# MCU_Module_V1.net
KiCad netlist of a schematic drawn in EAGLE
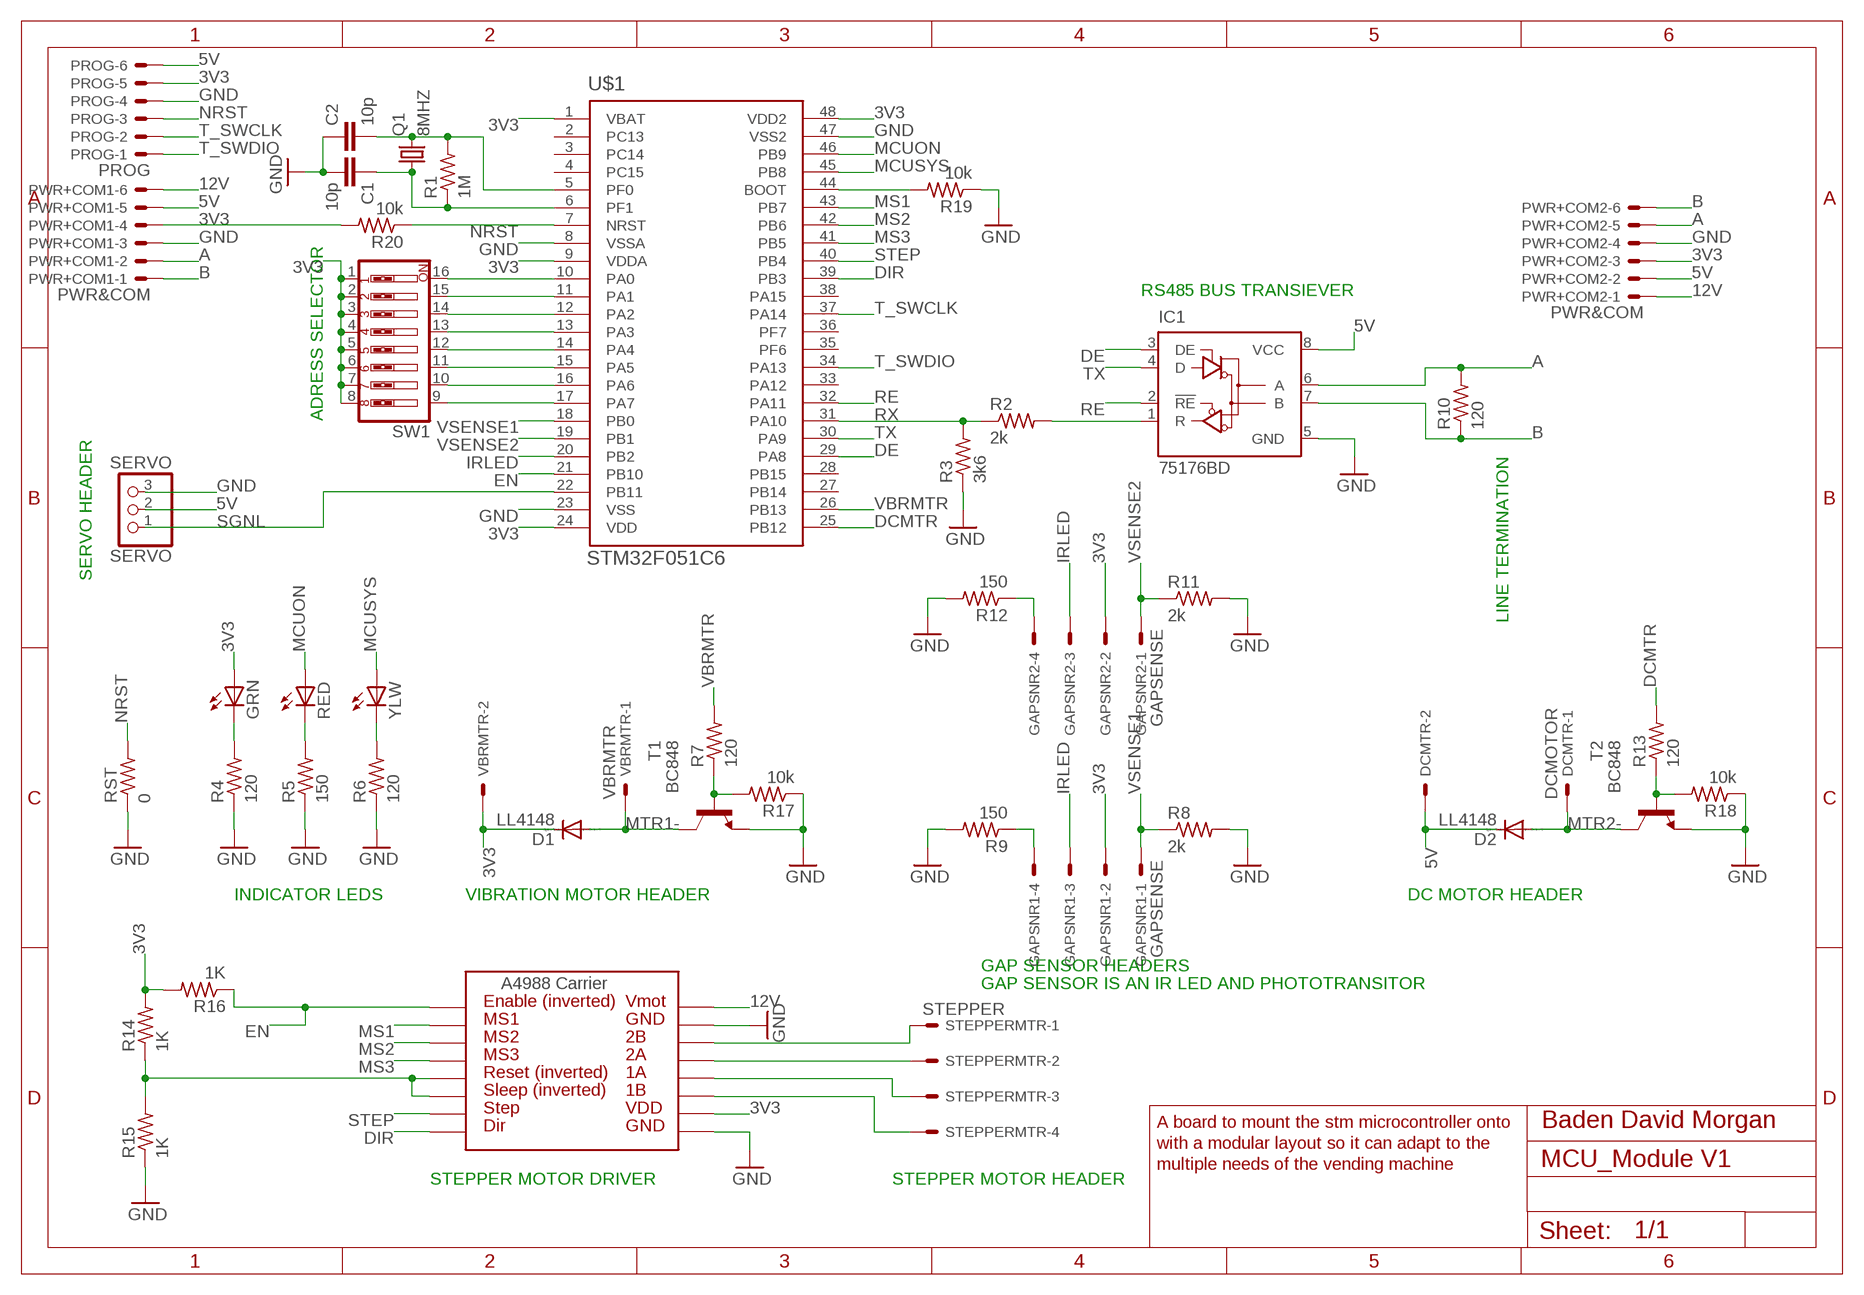
[diagram p0: schematic, sheet 1]

(export (version "E")
  (design (tool "Eeschema 10.0.6"))
  (components
    (comp (ref "C1")
      (value "10p")
      (footprint "eagle-import:C0805")
      (libsource (lib "eagle-import") (part "C-EUC0805"))
    )
    (comp (ref "C2")
      (value "10p")
      (footprint "eagle-import:C0805")
      (libsource (lib "eagle-import") (part "C-EUC0805"))
    )
    (comp (ref "D1")
      (value "LL4148")
      (footprint "eagle-import:SOD80C")
      (libsource (lib "eagle-import") (part "PMLL4150"))
    )
    (comp (ref "D2")
      (value "LL4148")
      (footprint "eagle-import:SOD80C")
      (libsource (lib "eagle-import") (part "PMLL4150"))
    )
    (comp (ref "DCMTR")
      (value "DCMOTOR")
      (footprint "eagle-import:6410-02")
      (libsource (lib "eagle-import") (part "22-?-0227-2021"))
    )
    (comp (ref "GAPSNR1")
      (value "GAPSENSE")
      (footprint "eagle-import:6410-04")
      (libsource (lib "eagle-import") (part "22-?-0427-2041"))
    )
    (comp (ref "GAPSNR2")
      (value "GAPSENSE")
      (footprint "eagle-import:6410-04")
      (libsource (lib "eagle-import") (part "22-?-0427-2041"))
    )
    (comp (ref "GRN")
      (value "LEDSML1206")
      (footprint "eagle-import:SML1206")
      (libsource (lib "eagle-import") (part "LEDSML1206"))
    )
    (comp (ref "IC1")
      (value "75176BD")
      (footprint "eagle-import:D_R-PDSO-G8")
      (libsource (lib "eagle-import") (part "75176AD"))
    )
    (comp (ref "PROG")
      (value "PROG")
      (footprint "eagle-import:6410-06")
      (libsource (lib "eagle-import") (part "22-?-0627-2061"))
    )
    (comp (ref "PWR+COM1")
      (value "PWR&COM")
      (footprint "eagle-import:7395-06")
      (libsource (lib "eagle-import") (part "22-?-0605-7068"))
    )
    (comp (ref "PWR+COM2")
      (value "PWR&COM")
      (footprint "eagle-import:7395-06")
      (libsource (lib "eagle-import") (part "22-?-0605-7068"))
    )
    (comp (ref "Q1")
      (value "8MHZ")
      (footprint "eagle-import:SM49")
      (libsource (lib "eagle-import") (part "CRYSTALSM49"))
    )
    (comp (ref "R1")
      (value "1M")
      (footprint "eagle-import:R0805")
      (libsource (lib "eagle-import") (part "R-US_R0805"))
    )
    (comp (ref "R2")
      (value "2k")
      (footprint "eagle-import:R0805")
      (libsource (lib "eagle-import") (part "resistor_R-US_R0805"))
    )
    (comp (ref "R3")
      (value "3k6")
      (footprint "eagle-import:R0805")
      (libsource (lib "eagle-import") (part "resistor_R-US_R0805"))
    )
    (comp (ref "R4")
      (value "120")
      (footprint "eagle-import:R0805")
      (libsource (lib "eagle-import") (part "R-US_R0805"))
    )
    (comp (ref "R5")
      (value "150")
      (footprint "eagle-import:R0805")
      (libsource (lib "eagle-import") (part "R-US_R0805"))
    )
    (comp (ref "R6")
      (value "120")
      (footprint "eagle-import:R0805")
      (libsource (lib "eagle-import") (part "R-US_R0805"))
    )
    (comp (ref "R7")
      (value "120")
      (footprint "eagle-import:R0805")
      (libsource (lib "eagle-import") (part "R-US_R0805"))
    )
    (comp (ref "R8")
      (value "2k")
      (footprint "eagle-import:R0805")
      (libsource (lib "eagle-import") (part "resistor_R-US_R0805"))
    )
    (comp (ref "R9")
      (value "150")
      (footprint "eagle-import:R0805")
      (libsource (lib "eagle-import") (part "R-US_R0805"))
    )
    (comp (ref "R10")
      (value "120")
      (footprint "eagle-import:R0805")
      (libsource (lib "eagle-import") (part "resistor_R-US_R0805"))
    )
    (comp (ref "R11")
      (value "2k")
      (footprint "eagle-import:R0805")
      (libsource (lib "eagle-import") (part "resistor_R-US_R0805"))
    )
    (comp (ref "R12")
      (value "150")
      (footprint "eagle-import:R0805")
      (libsource (lib "eagle-import") (part "R-US_R0805"))
    )
    (comp (ref "R13")
      (value "120")
      (footprint "eagle-import:R0805")
      (libsource (lib "eagle-import") (part "R-US_R0805"))
    )
    (comp (ref "R14")
      (value "1K")
      (footprint "eagle-import:R0805")
      (libsource (lib "eagle-import") (part "R-US_R0805"))
    )
    (comp (ref "R15")
      (value "1K")
      (footprint "eagle-import:R0805")
      (libsource (lib "eagle-import") (part "R-US_R0805"))
    )
    (comp (ref "R16")
      (value "1K")
      (footprint "eagle-import:R0805")
      (libsource (lib "eagle-import") (part "R-US_R0805"))
    )
    (comp (ref "R17")
      (value "10k")
      (footprint "eagle-import:R0805")
      (libsource (lib "eagle-import") (part "R-US_R0805"))
    )
    (comp (ref "R18")
      (value "10k")
      (footprint "eagle-import:R0805")
      (libsource (lib "eagle-import") (part "R-US_R0805"))
    )
    (comp (ref "R19")
      (value "10k")
      (footprint "eagle-import:R0805")
      (libsource (lib "eagle-import") (part "R-US_R0805"))
    )
    (comp (ref "R20")
      (value "10k")
      (footprint "eagle-import:R0805")
      (libsource (lib "eagle-import") (part "R-US_R0805"))
    )
    (comp (ref "RED")
      (value "LEDSML1206")
      (footprint "eagle-import:SML1206")
      (libsource (lib "eagle-import") (part "LEDSML1206"))
    )
    (comp (ref "RST")
      (value "0")
      (footprint "eagle-import:R0805")
      (libsource (lib "eagle-import") (part "R-US_R0805"))
    )
    (comp (ref "SERVO")
      (value "SERVO")
      (footprint "eagle-import:1X03")
      (libsource (lib "eagle-import") (part "PINHD-1X3"))
    )
    (comp (ref "STEPPERMTR")
      (value "STEPPER")
      (footprint "eagle-import:6410-04")
      (libsource (lib "eagle-import") (part "22-?-0427-2041"))
    )
    (comp (ref "SW1")
      (value "SW_DIP-8")
      (footprint "eagle-import:EDG-08")
      (libsource (lib "eagle-import") (part "SW_DIP-8"))
    )
    (comp (ref "T1")
      (value "BC848")
      (footprint "eagle-import:SOT23")
      (libsource (lib "eagle-import") (part "BC848"))
    )
    (comp (ref "T2")
      (value "BC848")
      (footprint "eagle-import:SOT23")
      (libsource (lib "eagle-import") (part "BC848"))
    )
    (comp (ref "U$1")
      (value "STM32F051C6")
      (footprint "eagle-import:QFP50P900X900X160-48N")
      (libsource (lib "eagle-import") (part "STM32F051C6"))
    )
    (comp (ref "U$2")
      (value "A4983CARRIER")
      (footprint "eagle-import:A4988BREAKOUT")
      (libsource (lib "eagle-import") (part "A4983CARRIER"))
    )
    (comp (ref "VBRMTR")
      (value "VBRMTR")
      (footprint "eagle-import:6410-02")
      (libsource (lib "eagle-import") (part "22-?-0227-2021"))
    )
    (comp (ref "YLW")
      (value "LEDSML1206")
      (footprint "eagle-import:SML1206")
      (libsource (lib "eagle-import") (part "LEDSML1206"))
    )
  )
  (nets
    (net (code "1") (name "/3V3") (class "Default")
      (node (ref "D1") (pin "C") (pinfunction "C_C") (pintype "passive"))
      (node (ref "GAPSNR1") (pin "2") (pinfunction "S_2") (pintype "passive"))
      (node (ref "GAPSNR2") (pin "2") (pinfunction "S_2") (pintype "passive"))
      (node (ref "GRN") (pin "A") (pinfunction "A_A") (pintype "passive"))
      (node (ref "PROG") (pin "5") (pinfunction "S_5") (pintype "passive"))
      (node (ref "PWR+COM1") (pin "4") (pinfunction "S_4") (pintype "passive"))
      (node (ref "PWR+COM2") (pin "3") (pinfunction "S_3") (pintype "passive"))
      (node (ref "R14") (pin "2") (pinfunction "2_2") (pintype "passive"))
      (node (ref "R16") (pin "2") (pinfunction "2_2") (pintype "passive"))
      (node (ref "R20") (pin "2") (pinfunction "2_2") (pintype "passive"))
      (node (ref "SW1") (pin "1") (pinfunction "1_1") (pintype "passive"))
      (node (ref "SW1") (pin "2") (pinfunction "2_2") (pintype "passive"))
      (node (ref "SW1") (pin "3") (pinfunction "3_3") (pintype "passive"))
      (node (ref "SW1") (pin "4") (pinfunction "4_4") (pintype "passive"))
      (node (ref "SW1") (pin "5") (pinfunction "5_5") (pintype "passive"))
      (node (ref "SW1") (pin "6") (pinfunction "6_6") (pintype "passive"))
      (node (ref "SW1") (pin "7") (pinfunction "7_7") (pintype "passive"))
      (node (ref "SW1") (pin "8") (pinfunction "8_8") (pintype "passive"))
      (node (ref "U$1") (pin "1") (pinfunction "VBAT_1") (pintype "bidirectional"))
      (node (ref "U$1") (pin "24") (pinfunction "VDD_24") (pintype "bidirectional"))
      (node (ref "U$1") (pin "48") (pinfunction "VDD2_48") (pintype "bidirectional"))
      (node (ref "U$1") (pin "9") (pinfunction "VDDA_9") (pintype "bidirectional"))
      (node (ref "U$2") (pin "VDD") (pinfunction "VDD_VDD") (pintype "power_in"))
      (node (ref "VBRMTR") (pin "2") (pinfunction "S_2") (pintype "passive"))
    )
    (net (code "2") (name "/5V") (class "Default")
      (node (ref "D2") (pin "C") (pinfunction "C_C") (pintype "passive"))
      (node (ref "DCMTR") (pin "2") (pinfunction "S_2") (pintype "passive"))
      (node (ref "IC1") (pin "8") (pinfunction "VCC_8") (pintype "power_in"))
      (node (ref "PROG") (pin "6") (pinfunction "S_6") (pintype "passive"))
      (node (ref "PWR+COM1") (pin "5") (pinfunction "S_5") (pintype "passive"))
      (node (ref "PWR+COM2") (pin "2") (pinfunction "S_2") (pintype "passive"))
      (node (ref "SERVO") (pin "2") (pinfunction "2_2") (pintype "passive"))
    )
    (net (code "3") (name "/12V") (class "Default")
      (node (ref "PWR+COM1") (pin "6") (pinfunction "S_6") (pintype "passive"))
      (node (ref "PWR+COM2") (pin "1") (pinfunction "S_1") (pintype "passive"))
      (node (ref "U$2") (pin "VMOT") (pinfunction "VMOT_VMOT") (pintype "power_in"))
    )
    (net (code "4") (name "/A") (class "Default")
      (node (ref "IC1") (pin "6") (pinfunction "A_6") (pintype "output"))
      (node (ref "PWR+COM1") (pin "2") (pinfunction "S_2") (pintype "passive"))
      (node (ref "PWR+COM2") (pin "5") (pinfunction "S_5") (pintype "passive"))
      (node (ref "R10") (pin "2") (pinfunction "2_2") (pintype "passive"))
    )
    (net (code "5") (name "/B") (class "Default")
      (node (ref "IC1") (pin "7") (pinfunction "B_7") (pintype "output"))
      (node (ref "PWR+COM1") (pin "1") (pinfunction "S_1") (pintype "passive"))
      (node (ref "PWR+COM2") (pin "6") (pinfunction "S_6") (pintype "passive"))
      (node (ref "R10") (pin "1") (pinfunction "1_1") (pintype "passive"))
    )
    (net (code "6") (name "/DCMTR") (class "Default")
      (node (ref "R13") (pin "2") (pinfunction "2_2") (pintype "passive"))
      (node (ref "U$1") (pin "25") (pinfunction "PB12_25") (pintype "bidirectional"))
    )
    (net (code "7") (name "/DE") (class "Default")
      (node (ref "IC1") (pin "3") (pinfunction "DE_3") (pintype "input"))
      (node (ref "U$1") (pin "29") (pinfunction "PA8_29") (pintype "bidirectional"))
    )
    (net (code "8") (name "/DIR") (class "Default")
      (node (ref "U$1") (pin "39") (pinfunction "PB3_39") (pintype "bidirectional"))
      (node (ref "U$2") (pin "DIR") (pinfunction "DIR_DIR") (pintype "input"))
    )
    (net (code "9") (name "/EN") (class "Default")
      (node (ref "R16") (pin "1") (pinfunction "1_1") (pintype "passive"))
      (node (ref "U$1") (pin "21") (pinfunction "PB10_21") (pintype "bidirectional"))
      (node (ref "U$2") (pin "EN") (pinfunction "EN_EN") (pintype "input"))
    )
    (net (code "10") (name "/IRLED") (class "Default")
      (node (ref "GAPSNR1") (pin "3") (pinfunction "S_3") (pintype "passive"))
      (node (ref "GAPSNR2") (pin "3") (pinfunction "S_3") (pintype "passive"))
      (node (ref "U$1") (pin "20") (pinfunction "PB2_20") (pintype "bidirectional"))
    )
    (net (code "11") (name "/MCUON") (class "Default")
      (node (ref "RED") (pin "A") (pinfunction "A_A") (pintype "passive"))
      (node (ref "U$1") (pin "46") (pinfunction "PB9_46") (pintype "bidirectional"))
    )
    (net (code "12") (name "/MCUSYS") (class "Default")
      (node (ref "U$1") (pin "45") (pinfunction "PB8_45") (pintype "bidirectional"))
      (node (ref "YLW") (pin "A") (pinfunction "A_A") (pintype "passive"))
    )
    (net (code "13") (name "/MS1") (class "Default")
      (node (ref "U$1") (pin "43") (pinfunction "PB7_43") (pintype "bidirectional"))
      (node (ref "U$2") (pin "MS1") (pinfunction "MS1_MS1") (pintype "input"))
    )
    (net (code "14") (name "/MS2") (class "Default")
      (node (ref "U$1") (pin "42") (pinfunction "PB6_42") (pintype "bidirectional"))
      (node (ref "U$2") (pin "MS2") (pinfunction "MS2_MS2") (pintype "input"))
    )
    (net (code "15") (name "/MS3") (class "Default")
      (node (ref "U$1") (pin "41") (pinfunction "PB5_41") (pintype "bidirectional"))
      (node (ref "U$2") (pin "MS3") (pinfunction "MS3_MS3") (pintype "input"))
    )
    (net (code "16") (name "/MTR1-") (class "Default")
      (node (ref "D1") (pin "A") (pinfunction "A_A") (pintype "passive"))
      (node (ref "T1") (pin "3") (pinfunction "C_3") (pintype "passive"))
      (node (ref "VBRMTR") (pin "1") (pinfunction "S_1") (pintype "passive"))
    )
    (net (code "17") (name "/MTR2-") (class "Default")
      (node (ref "D2") (pin "A") (pinfunction "A_A") (pintype "passive"))
      (node (ref "DCMTR") (pin "1") (pinfunction "S_1") (pintype "passive"))
      (node (ref "T2") (pin "3") (pinfunction "C_3") (pintype "passive"))
    )
    (net (code "18") (name "/NRST") (class "Default")
      (node (ref "PROG") (pin "3") (pinfunction "S_3") (pintype "passive"))
      (node (ref "R20") (pin "1") (pinfunction "1_1") (pintype "passive"))
      (node (ref "RST") (pin "2") (pinfunction "2_2") (pintype "passive"))
      (node (ref "U$1") (pin "7") (pinfunction "NRST_7") (pintype "bidirectional"))
    )
    (net (code "19") (name "/RE") (class "Default")
      (node (ref "IC1") (pin "2") (pinfunction "~{RE}_2") (pintype "input"))
      (node (ref "U$1") (pin "32") (pinfunction "PA11_32") (pintype "bidirectional"))
    )
    (net (code "20") (name "/RX") (class "Default")
      (node (ref "R2") (pin "1") (pinfunction "1_1") (pintype "passive"))
      (node (ref "R3") (pin "2") (pinfunction "2_2") (pintype "passive"))
      (node (ref "U$1") (pin "31") (pinfunction "PA10_31") (pintype "bidirectional"))
    )
    (net (code "21") (name "/SGNL") (class "Default")
      (node (ref "SERVO") (pin "1") (pinfunction "1_1") (pintype "passive"))
      (node (ref "U$1") (pin "22") (pinfunction "PB11_22") (pintype "bidirectional"))
    )
    (net (code "22") (name "/STEP") (class "Default")
      (node (ref "U$1") (pin "40") (pinfunction "PB4_40") (pintype "bidirectional"))
      (node (ref "U$2") (pin "STEP") (pinfunction "STEP_STEP") (pintype "input"))
    )
    (net (code "23") (name "/TX") (class "Default")
      (node (ref "IC1") (pin "4") (pinfunction "D_4") (pintype "input"))
      (node (ref "U$1") (pin "30") (pinfunction "PA9_30") (pintype "bidirectional"))
    )
    (net (code "24") (name "/T_SWCLK") (class "Default")
      (node (ref "PROG") (pin "2") (pinfunction "S_2") (pintype "passive"))
      (node (ref "U$1") (pin "37") (pinfunction "PA14_37") (pintype "bidirectional"))
    )
    (net (code "25") (name "/T_SWDIO") (class "Default")
      (node (ref "PROG") (pin "1") (pinfunction "S_1") (pintype "passive"))
      (node (ref "U$1") (pin "34") (pinfunction "PA13_34") (pintype "bidirectional"))
    )
    (net (code "26") (name "/VBRMTR") (class "Default")
      (node (ref "R7") (pin "2") (pinfunction "2_2") (pintype "passive"))
      (node (ref "U$1") (pin "26") (pinfunction "PB13_26") (pintype "bidirectional"))
    )
    (net (code "27") (name "/VSENSE1") (class "Default")
      (node (ref "GAPSNR1") (pin "1") (pinfunction "S_1") (pintype "passive"))
      (node (ref "R8") (pin "1") (pinfunction "1_1") (pintype "passive"))
      (node (ref "U$1") (pin "18") (pinfunction "PB0_18") (pintype "bidirectional"))
    )
    (net (code "28") (name "/VSENSE2") (class "Default")
      (node (ref "GAPSNR2") (pin "1") (pinfunction "S_1") (pintype "passive"))
      (node (ref "R11") (pin "1") (pinfunction "1_1") (pintype "passive"))
      (node (ref "U$1") (pin "19") (pinfunction "PB1_19") (pintype "bidirectional"))
    )
    (net (code "29") (name "GND") (class "Default")
      (node (ref "C1") (pin "2") (pinfunction "2_2") (pintype "passive"))
      (node (ref "C2") (pin "1") (pinfunction "1_1") (pintype "passive"))
      (node (ref "IC1") (pin "5") (pinfunction "GND_5") (pintype "power_in"))
      (node (ref "PROG") (pin "4") (pinfunction "S_4") (pintype "passive"))
      (node (ref "PWR+COM1") (pin "3") (pinfunction "S_3") (pintype "passive"))
      (node (ref "PWR+COM2") (pin "4") (pinfunction "S_4") (pintype "passive"))
      (node (ref "R11") (pin "2") (pinfunction "2_2") (pintype "passive"))
      (node (ref "R12") (pin "2") (pinfunction "2_2") (pintype "passive"))
      (node (ref "R15") (pin "1") (pinfunction "1_1") (pintype "passive"))
      (node (ref "R17") (pin "1") (pinfunction "1_1") (pintype "passive"))
      (node (ref "R18") (pin "1") (pinfunction "1_1") (pintype "passive"))
      (node (ref "R19") (pin "1") (pinfunction "1_1") (pintype "passive"))
      (node (ref "R3") (pin "1") (pinfunction "1_1") (pintype "passive"))
      (node (ref "R4") (pin "1") (pinfunction "1_1") (pintype "passive"))
      (node (ref "R5") (pin "1") (pinfunction "1_1") (pintype "passive"))
      (node (ref "R6") (pin "1") (pinfunction "1_1") (pintype "passive"))
      (node (ref "R8") (pin "2") (pinfunction "2_2") (pintype "passive"))
      (node (ref "R9") (pin "2") (pinfunction "2_2") (pintype "passive"))
      (node (ref "RST") (pin "1") (pinfunction "1_1") (pintype "passive"))
      (node (ref "SERVO") (pin "3") (pinfunction "3_3") (pintype "passive"))
      (node (ref "T1") (pin "2") (pinfunction "E_2") (pintype "passive"))
      (node (ref "T2") (pin "2") (pinfunction "E_2") (pintype "passive"))
      (node (ref "U$1") (pin "23") (pinfunction "VSS_23") (pintype "bidirectional"))
      (node (ref "U$1") (pin "47") (pinfunction "VSS2_47") (pintype "bidirectional"))
      (node (ref "U$1") (pin "8") (pinfunction "VSSA_8") (pintype "bidirectional"))
      (node (ref "U$2") (pin "GND") (pinfunction "GND_GND") (pintype "power_in"))
      (node (ref "U$2") (pin "GND@0") (pinfunction "GND_GND@0") (pintype "power_in"))
    )
    (net (code "30") (name "Net-(GAPSNR1D-S)") (class "Default")
      (node (ref "GAPSNR1") (pin "4") (pinfunction "S_4") (pintype "passive"))
      (node (ref "R9") (pin "1") (pinfunction "1_1") (pintype "passive"))
    )
    (net (code "31") (name "Net-(GAPSNR2D-S)") (class "Default")
      (node (ref "GAPSNR2") (pin "4") (pinfunction "S_4") (pintype "passive"))
      (node (ref "R12") (pin "1") (pinfunction "1_1") (pintype "passive"))
    )
    (net (code "32") (name "Net-(GRN-PadC)") (class "Default")
      (node (ref "GRN") (pin "C") (pinfunction "C_C") (pintype "passive"))
      (node (ref "R4") (pin "2") (pinfunction "2_2") (pintype "passive"))
    )
    (net (code "33") (name "Net-(IC1-R)") (class "Default")
      (node (ref "IC1") (pin "1") (pinfunction "R_1") (pintype "input"))
      (node (ref "R2") (pin "2") (pinfunction "2_2") (pintype "passive"))
    )
    (net (code "34") (name "Net-(R5-Pad2)") (class "Default")
      (node (ref "R5") (pin "2") (pinfunction "2_2") (pintype "passive"))
      (node (ref "RED") (pin "C") (pinfunction "C_C") (pintype "passive"))
    )
    (net (code "35") (name "Net-(R6-Pad2)") (class "Default")
      (node (ref "R6") (pin "2") (pinfunction "2_2") (pintype "passive"))
      (node (ref "YLW") (pin "C") (pinfunction "C_C") (pintype "passive"))
    )
    (net (code "36") (name "Net-(STEPPERMTRA-S)") (class "Default")
      (node (ref "STEPPERMTR") (pin "1") (pinfunction "S_1") (pintype "passive"))
      (node (ref "U$2") (pin "2B") (pinfunction "2B_2B") (pintype "output"))
    )
    (net (code "37") (name "Net-(STEPPERMTRB-S)") (class "Default")
      (node (ref "STEPPERMTR") (pin "2") (pinfunction "S_2") (pintype "passive"))
      (node (ref "U$2") (pin "2A") (pinfunction "2A_2A") (pintype "output"))
    )
    (net (code "38") (name "Net-(STEPPERMTRC-S)") (class "Default")
      (node (ref "STEPPERMTR") (pin "3") (pinfunction "S_3") (pintype "passive"))
      (node (ref "U$2") (pin "1A") (pinfunction "1A_1A") (pintype "output"))
    )
    (net (code "39") (name "Net-(STEPPERMTRD-S)") (class "Default")
      (node (ref "STEPPERMTR") (pin "4") (pinfunction "S_4") (pintype "passive"))
      (node (ref "U$2") (pin "1B") (pinfunction "1B_1B") (pintype "output"))
    )
    (net (code "40") (name "Net-(T1-B)") (class "Default")
      (node (ref "R17") (pin "2") (pinfunction "2_2") (pintype "passive"))
      (node (ref "R7") (pin "1") (pinfunction "1_1") (pintype "passive"))
      (node (ref "T1") (pin "1") (pinfunction "B_1") (pintype "passive"))
    )
    (net (code "41") (name "Net-(T2-B)") (class "Default")
      (node (ref "R13") (pin "1") (pinfunction "1_1") (pintype "passive"))
      (node (ref "R18") (pin "2") (pinfunction "2_2") (pintype "passive"))
      (node (ref "T2") (pin "1") (pinfunction "B_1") (pintype "passive"))
    )
    (net (code "42") (name "Net-(U$1-BOOT)") (class "Default")
      (node (ref "R19") (pin "2") (pinfunction "2_2") (pintype "passive"))
      (node (ref "U$1") (pin "44") (pinfunction "BOOT_44") (pintype "bidirectional"))
    )
    (net (code "43") (name "Net-(U$1-PA0)") (class "Default")
      (node (ref "SW1") (pin "16") (pinfunction "16_16") (pintype "passive"))
      (node (ref "U$1") (pin "10") (pinfunction "PA0_10") (pintype "bidirectional"))
    )
    (net (code "44") (name "Net-(U$1-PA1)") (class "Default")
      (node (ref "SW1") (pin "15") (pinfunction "15_15") (pintype "passive"))
      (node (ref "U$1") (pin "11") (pinfunction "PA1_11") (pintype "bidirectional"))
    )
    (net (code "45") (name "Net-(U$1-PA2)") (class "Default")
      (node (ref "SW1") (pin "14") (pinfunction "14_14") (pintype "passive"))
      (node (ref "U$1") (pin "12") (pinfunction "PA2_12") (pintype "bidirectional"))
    )
    (net (code "46") (name "Net-(U$1-PA3)") (class "Default")
      (node (ref "SW1") (pin "13") (pinfunction "13_13") (pintype "passive"))
      (node (ref "U$1") (pin "13") (pinfunction "PA3_13") (pintype "bidirectional"))
    )
    (net (code "47") (name "Net-(U$1-PA4)") (class "Default")
      (node (ref "SW1") (pin "12") (pinfunction "12_12") (pintype "passive"))
      (node (ref "U$1") (pin "14") (pinfunction "PA4_14") (pintype "bidirectional"))
    )
    (net (code "48") (name "Net-(U$1-PA5)") (class "Default")
      (node (ref "SW1") (pin "11") (pinfunction "11_11") (pintype "passive"))
      (node (ref "U$1") (pin "15") (pinfunction "PA5_15") (pintype "bidirectional"))
    )
    (net (code "49") (name "Net-(U$1-PA6)") (class "Default")
      (node (ref "SW1") (pin "10") (pinfunction "10_10") (pintype "passive"))
      (node (ref "U$1") (pin "16") (pinfunction "PA6_16") (pintype "bidirectional"))
    )
    (net (code "50") (name "Net-(U$1-PA7)") (class "Default")
      (node (ref "SW1") (pin "9") (pinfunction "9_9") (pintype "passive"))
      (node (ref "U$1") (pin "17") (pinfunction "PA7_17") (pintype "bidirectional"))
    )
    (net (code "51") (name "Net-(U$1-PF0)") (class "Default")
      (node (ref "C2") (pin "2") (pinfunction "2_2") (pintype "passive"))
      (node (ref "Q1") (pin "2") (pinfunction "2_2") (pintype "passive"))
      (node (ref "R1") (pin "2") (pinfunction "2_2") (pintype "passive"))
      (node (ref "U$1") (pin "5") (pinfunction "PF0_5") (pintype "bidirectional"))
    )
    (net (code "52") (name "Net-(U$1-PF1)") (class "Default")
      (node (ref "C1") (pin "1") (pinfunction "1_1") (pintype "passive"))
      (node (ref "Q1") (pin "1") (pinfunction "1_1") (pintype "passive"))
      (node (ref "R1") (pin "1") (pinfunction "1_1") (pintype "passive"))
      (node (ref "U$1") (pin "6") (pinfunction "PF1_6") (pintype "bidirectional"))
    )
    (net (code "53") (name "Net-(U$2-SLEEP)") (class "Default")
      (node (ref "R14") (pin "1") (pinfunction "1_1") (pintype "passive"))
      (node (ref "R15") (pin "2") (pinfunction "2_2") (pintype "passive"))
      (node (ref "U$2") (pin "RST") (pinfunction "RST_RST") (pintype "input"))
      (node (ref "U$2") (pin "SLP") (pinfunction "SLEEP_SLP") (pintype "input"))
    )
    (net (code "54") (name "unconnected-(U$1-PA12-Pad33)") (class "Default")
      (node (ref "U$1") (pin "33") (pinfunction "PA12_33") (pintype "bidirectional"))
    )
    (net (code "55") (name "unconnected-(U$1-PA15-Pad38)") (class "Default")
      (node (ref "U$1") (pin "38") (pinfunction "PA15_38") (pintype "bidirectional"))
    )
    (net (code "56") (name "unconnected-(U$1-PB14-Pad27)") (class "Default")
      (node (ref "U$1") (pin "27") (pinfunction "PB14_27") (pintype "bidirectional"))
    )
    (net (code "57") (name "unconnected-(U$1-PB15-Pad28)") (class "Default")
      (node (ref "U$1") (pin "28") (pinfunction "PB15_28") (pintype "bidirectional"))
    )
    (net (code "58") (name "unconnected-(U$1-PC13-Pad2)") (class "Default")
      (node (ref "U$1") (pin "2") (pinfunction "PC13_2") (pintype "bidirectional"))
    )
    (net (code "59") (name "unconnected-(U$1-PC14-Pad3)") (class "Default")
      (node (ref "U$1") (pin "3") (pinfunction "PC14_3") (pintype "bidirectional"))
    )
    (net (code "60") (name "unconnected-(U$1-PC15-Pad4)") (class "Default")
      (node (ref "U$1") (pin "4") (pinfunction "PC15_4") (pintype "bidirectional"))
    )
    (net (code "61") (name "unconnected-(U$1-PF6-Pad35)") (class "Default")
      (node (ref "U$1") (pin "35") (pinfunction "PF6_35") (pintype "bidirectional"))
    )
    (net (code "62") (name "unconnected-(U$1-PF7-Pad36)") (class "Default")
      (node (ref "U$1") (pin "36") (pinfunction "PF7_36") (pintype "bidirectional"))
    )
  )
)
